# stm32h750ibk6-pwr.net
KiCad netlist of a schematic drawn in Altium Designer
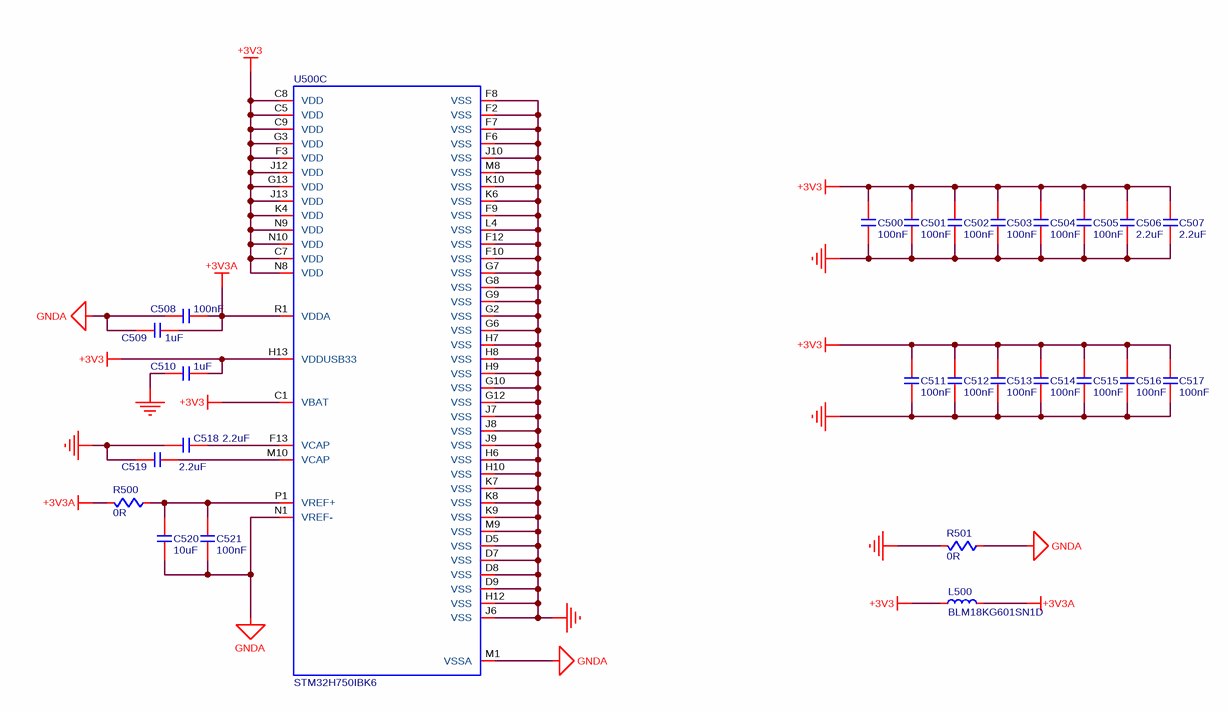
[diagram p0: stm32h750ibk6-pwr.SchDoc]

(export (version "E")
  (design (tool "Eeschema 10.0.6"))
  (components
    (comp (ref "C500")
      (value "100nF")
      (footprint "mw:C0402")
      (fields (field (name "VOLTAGE") "25V") (field (name "Comment") "C-NOMO"))
      (libsource (lib "mw") (part "C-NOMO"))
    )
    (comp (ref "C501")
      (value "100nF")
      (footprint "mw:C0402")
      (fields (field (name "VOLTAGE") "25V") (field (name "Comment") "C-NOMO"))
      (libsource (lib "mw") (part "C-NOMO"))
    )
    (comp (ref "C502")
      (value "100nF")
      (footprint "mw:C0402")
      (fields (field (name "VOLTAGE") "25V") (field (name "Comment") "C-NOMO"))
      (libsource (lib "mw") (part "C-NOMO"))
    )
    (comp (ref "C503")
      (value "100nF")
      (footprint "mw:C0402")
      (fields (field (name "VOLTAGE") "25V") (field (name "Comment") "C-NOMO"))
      (libsource (lib "mw") (part "C-NOMO"))
    )
    (comp (ref "C504")
      (value "100nF")
      (footprint "mw:C0402")
      (fields (field (name "VOLTAGE") "25V") (field (name "Comment") "C-NOMO"))
      (libsource (lib "mw") (part "C-NOMO"))
    )
    (comp (ref "C505")
      (value "100nF")
      (footprint "mw:C0402")
      (fields (field (name "VOLTAGE") "25V") (field (name "Comment") "C-NOMO"))
      (libsource (lib "mw") (part "C-NOMO"))
    )
    (comp (ref "C506")
      (value "2.2uF")
      (footprint "mw:C0603")
      (fields (field (name "VOLTAGE") "25V") (field (name "Comment") "C-NOMO"))
      (libsource (lib "mw") (part "C-NOMO"))
    )
    (comp (ref "C507")
      (value "2.2uF")
      (footprint "mw:C0603")
      (fields (field (name "VOLTAGE") "25V") (field (name "Comment") "C-NOMO"))
      (libsource (lib "mw") (part "C-NOMO"))
    )
    (comp (ref "C508")
      (value "1uF")
      (footprint "mw:C0603")
      (fields (field (name "VOLTAGE") "25V") (field (name "Comment") "C-NOMO"))
      (libsource (lib "mw") (part "C-NOMO"))
    )
    (comp (ref "C509")
      (value "100nF")
      (footprint "mw:C0402")
      (fields (field (name "VOLTAGE") "25V") (field (name "Comment") "C-NOMO"))
      (libsource (lib "mw") (part "C-NOMO"))
    )
    (comp (ref "C510")
      (value "1uF")
      (footprint "mw:C0603")
      (fields (field (name "VOLTAGE") "25V") (field (name "Comment") "C-NOMO"))
      (libsource (lib "mw") (part "C-NOMO"))
    )
    (comp (ref "C511")
      (value "100nF")
      (footprint "mw:C0402")
      (fields (field (name "VOLTAGE") "25V") (field (name "Comment") "C-NOMO"))
      (libsource (lib "mw") (part "C-NOMO"))
    )
    (comp (ref "C512")
      (value "100nF")
      (footprint "mw:C0402")
      (fields (field (name "VOLTAGE") "25V") (field (name "Comment") "C-NOMO"))
      (libsource (lib "mw") (part "C-NOMO"))
    )
    (comp (ref "C513")
      (value "100nF")
      (footprint "mw:C0402")
      (fields (field (name "VOLTAGE") "25V") (field (name "Comment") "C-NOMO"))
      (libsource (lib "mw") (part "C-NOMO"))
    )
    (comp (ref "C514")
      (value "100nF")
      (footprint "mw:C0402")
      (fields (field (name "VOLTAGE") "25V") (field (name "Comment") "C-NOMO"))
      (libsource (lib "mw") (part "C-NOMO"))
    )
    (comp (ref "C515")
      (value "100nF")
      (footprint "mw:C0402")
      (fields (field (name "VOLTAGE") "25V") (field (name "Comment") "C-NOMO"))
      (libsource (lib "mw") (part "C-NOMO"))
    )
    (comp (ref "C516")
      (value "100nF")
      (footprint "mw:C0402")
      (fields (field (name "VOLTAGE") "25V") (field (name "Comment") "C-NOMO"))
      (libsource (lib "mw") (part "C-NOMO"))
    )
    (comp (ref "C517")
      (value "100nF")
      (footprint "mw:C0402")
      (fields (field (name "VOLTAGE") "25V") (field (name "Comment") "C-NOMO"))
      (libsource (lib "mw") (part "C-NOMO"))
    )
    (comp (ref "C518")
      (value "2.2uF")
      (footprint "mw:C0603")
      (fields (field (name "VOLTAGE") "25V") (field (name "Comment") "C-NOMO"))
      (libsource (lib "mw") (part "C-NOMO"))
    )
    (comp (ref "C519")
      (value "2.2uF")
      (footprint "mw:C0603")
      (fields (field (name "VOLTAGE") "25V") (field (name "Comment") "C-NOMO"))
      (libsource (lib "mw") (part "C-NOMO"))
    )
    (comp (ref "C520")
      (value "10uF")
      (footprint "mw:C0603")
      (fields (field (name "VOLTAGE") "25V") (field (name "Comment") "C-NOMO"))
      (libsource (lib "mw") (part "C-NOMO"))
    )
    (comp (ref "C521")
      (value "100nF")
      (footprint "mw:C0402")
      (fields (field (name "VOLTAGE") "25V") (field (name "Comment") "C-NOMO"))
      (libsource (lib "mw") (part "C-NOMO"))
    )
    (comp (ref "L500")
      (value "BLM18KG601SN1D")
      (footprint "mw:L0603")
      (fields (field (name "PUBLISHER") "Altium Limited"))
      (libsource (lib "mw") (part "L"))
    )
    (comp (ref "R500")
      (value "0R")
      (footprint "mw:R0603")
      (fields (field (name "Comment") "R"))
      (libsource (lib "mw") (part "R"))
    )
    (comp (ref "R501")
      (value "0R")
      (footprint "mw:R0603")
      (fields (field (name "Comment") "R"))
      (libsource (lib "mw") (part "R"))
    )
    (comp (ref "U500")
      (value "STM32H750IBK6")
      (footprint "mw:STM32H750IBK6")
      (libsource (lib "mw") (part "STM32H750IBK6"))
    )
  )
  (nets
    (net (code "1") (name "+3V3") (class "Default")
      (node (ref "C500") (pin "2") (pinfunction "2_2") (pintype "passive"))
      (node (ref "C501") (pin "2") (pinfunction "2_2") (pintype "passive"))
      (node (ref "C502") (pin "2") (pinfunction "2_2") (pintype "passive"))
      (node (ref "C503") (pin "2") (pinfunction "2_2") (pintype "passive"))
      (node (ref "C504") (pin "2") (pinfunction "2_2") (pintype "passive"))
      (node (ref "C505") (pin "2") (pinfunction "2_2") (pintype "passive"))
      (node (ref "C506") (pin "2") (pinfunction "2_2") (pintype "passive"))
      (node (ref "C507") (pin "2") (pinfunction "2_2") (pintype "passive"))
      (node (ref "C510") (pin "1") (pinfunction "1_1") (pintype "passive"))
      (node (ref "C511") (pin "2") (pinfunction "2_2") (pintype "passive"))
      (node (ref "C512") (pin "2") (pinfunction "2_2") (pintype "passive"))
      (node (ref "C513") (pin "2") (pinfunction "2_2") (pintype "passive"))
      (node (ref "C514") (pin "2") (pinfunction "2_2") (pintype "passive"))
      (node (ref "C515") (pin "2") (pinfunction "2_2") (pintype "passive"))
      (node (ref "C516") (pin "2") (pinfunction "2_2") (pintype "passive"))
      (node (ref "C517") (pin "2") (pinfunction "2_2") (pintype "passive"))
      (node (ref "L500") (pin "1") (pinfunction "1_1") (pintype "passive"))
      (node (ref "U500") (pin "C1") (pinfunction "VBAT_C1") (pintype "passive"))
      (node (ref "U500") (pin "C5") (pinfunction "VDD_C5") (pintype "passive"))
      (node (ref "U500") (pin "C7") (pinfunction "VDD_C7") (pintype "passive"))
      (node (ref "U500") (pin "C8") (pinfunction "VDD_C8") (pintype "passive"))
      (node (ref "U500") (pin "C9") (pinfunction "VDD_C9") (pintype "passive"))
      (node (ref "U500") (pin "F3") (pinfunction "VDD_F3") (pintype "passive"))
      (node (ref "U500") (pin "G13") (pinfunction "VDD_G13") (pintype "passive"))
      (node (ref "U500") (pin "G3") (pinfunction "VDD_G3") (pintype "passive"))
      (node (ref "U500") (pin "H13") (pinfunction "VDDUSB33_H13") (pintype "passive"))
      (node (ref "U500") (pin "J12") (pinfunction "VDD_J12") (pintype "passive"))
      (node (ref "U500") (pin "J13") (pinfunction "VDD_J13") (pintype "passive"))
      (node (ref "U500") (pin "K4") (pinfunction "VDD_K4") (pintype "passive"))
      (node (ref "U500") (pin "N10") (pinfunction "VDD_N10") (pintype "passive"))
      (node (ref "U500") (pin "N8") (pinfunction "VDD_N8") (pintype "passive"))
      (node (ref "U500") (pin "N9") (pinfunction "VDD_N9") (pintype "passive"))
    )
    (net (code "2") (name "+3V3A") (class "Default")
      (node (ref "C508") (pin "1") (pinfunction "1_1") (pintype "passive"))
      (node (ref "C509") (pin "1") (pinfunction "1_1") (pintype "passive"))
      (node (ref "L500") (pin "2") (pinfunction "2_2") (pintype "passive"))
      (node (ref "R500") (pin "1") (pinfunction "1_1") (pintype "passive"))
      (node (ref "U500") (pin "R1") (pinfunction "VDDA_R1") (pintype "passive"))
    )
    (net (code "3") (name "GND") (class "Default")
      (node (ref "C500") (pin "1") (pinfunction "1_1") (pintype "passive"))
      (node (ref "C501") (pin "1") (pinfunction "1_1") (pintype "passive"))
      (node (ref "C502") (pin "1") (pinfunction "1_1") (pintype "passive"))
      (node (ref "C503") (pin "1") (pinfunction "1_1") (pintype "passive"))
      (node (ref "C504") (pin "1") (pinfunction "1_1") (pintype "passive"))
      (node (ref "C505") (pin "1") (pinfunction "1_1") (pintype "passive"))
      (node (ref "C506") (pin "1") (pinfunction "1_1") (pintype "passive"))
      (node (ref "C507") (pin "1") (pinfunction "1_1") (pintype "passive"))
      (node (ref "C510") (pin "2") (pinfunction "2_2") (pintype "passive"))
      (node (ref "C511") (pin "1") (pinfunction "1_1") (pintype "passive"))
      (node (ref "C512") (pin "1") (pinfunction "1_1") (pintype "passive"))
      (node (ref "C513") (pin "1") (pinfunction "1_1") (pintype "passive"))
      (node (ref "C514") (pin "1") (pinfunction "1_1") (pintype "passive"))
      (node (ref "C515") (pin "1") (pinfunction "1_1") (pintype "passive"))
      (node (ref "C516") (pin "1") (pinfunction "1_1") (pintype "passive"))
      (node (ref "C517") (pin "1") (pinfunction "1_1") (pintype "passive"))
      (node (ref "C518") (pin "1") (pinfunction "1_1") (pintype "passive"))
      (node (ref "C519") (pin "1") (pinfunction "1_1") (pintype "passive"))
      (node (ref "R501") (pin "1") (pinfunction "1_1") (pintype "passive"))
      (node (ref "U500") (pin "D5") (pinfunction "VSS_D5") (pintype "passive"))
      (node (ref "U500") (pin "D7") (pinfunction "VSS_D7") (pintype "passive"))
      (node (ref "U500") (pin "D8") (pinfunction "VSS_D8") (pintype "passive"))
      (node (ref "U500") (pin "D9") (pinfunction "VSS_D9") (pintype "passive"))
      (node (ref "U500") (pin "F10") (pinfunction "VSS_F10") (pintype "passive"))
      (node (ref "U500") (pin "F12") (pinfunction "VSS_F12") (pintype "passive"))
      (node (ref "U500") (pin "F2") (pinfunction "VSS_F2") (pintype "passive"))
      (node (ref "U500") (pin "F6") (pinfunction "VSS_F6") (pintype "passive"))
      (node (ref "U500") (pin "F7") (pinfunction "VSS_F7") (pintype "passive"))
      (node (ref "U500") (pin "F8") (pinfunction "VSS_F8") (pintype "passive"))
      (node (ref "U500") (pin "F9") (pinfunction "VSS_F9") (pintype "passive"))
      (node (ref "U500") (pin "G10") (pinfunction "VSS_G10") (pintype "passive"))
      (node (ref "U500") (pin "G12") (pinfunction "VSS_G12") (pintype "passive"))
      (node (ref "U500") (pin "G2") (pinfunction "VSS_G2") (pintype "passive"))
      (node (ref "U500") (pin "G6") (pinfunction "VSS_G6") (pintype "passive"))
      (node (ref "U500") (pin "G7") (pinfunction "VSS_G7") (pintype "passive"))
      (node (ref "U500") (pin "G8") (pinfunction "VSS_G8") (pintype "passive"))
      (node (ref "U500") (pin "G9") (pinfunction "VSS_G9") (pintype "passive"))
      (node (ref "U500") (pin "H10") (pinfunction "VSS_H10") (pintype "passive"))
      (node (ref "U500") (pin "H12") (pinfunction "VSS_H12") (pintype "passive"))
      (node (ref "U500") (pin "H6") (pinfunction "VSS_H6") (pintype "passive"))
      (node (ref "U500") (pin "H7") (pinfunction "VSS_H7") (pintype "passive"))
      (node (ref "U500") (pin "H8") (pinfunction "VSS_H8") (pintype "passive"))
      (node (ref "U500") (pin "H9") (pinfunction "VSS_H9") (pintype "passive"))
      (node (ref "U500") (pin "J10") (pinfunction "VSS_J10") (pintype "passive"))
      (node (ref "U500") (pin "J6") (pinfunction "VSS_J6") (pintype "passive"))
      (node (ref "U500") (pin "J7") (pinfunction "VSS_J7") (pintype "passive"))
      (node (ref "U500") (pin "J8") (pinfunction "VSS_J8") (pintype "passive"))
      (node (ref "U500") (pin "J9") (pinfunction "VSS_J9") (pintype "passive"))
      (node (ref "U500") (pin "K10") (pinfunction "VSS_K10") (pintype "passive"))
      (node (ref "U500") (pin "K6") (pinfunction "VSS_K6") (pintype "passive"))
      (node (ref "U500") (pin "K7") (pinfunction "VSS_K7") (pintype "passive"))
      (node (ref "U500") (pin "K8") (pinfunction "VSS_K8") (pintype "passive"))
      (node (ref "U500") (pin "K9") (pinfunction "VSS_K9") (pintype "passive"))
      (node (ref "U500") (pin "L4") (pinfunction "VSS_L4") (pintype "passive"))
      (node (ref "U500") (pin "M8") (pinfunction "VSS_M8") (pintype "passive"))
      (node (ref "U500") (pin "M9") (pinfunction "VSS_M9") (pintype "passive"))
    )
    (net (code "4") (name "GNDA") (class "Default")
      (node (ref "C508") (pin "2") (pinfunction "2_2") (pintype "passive"))
      (node (ref "C509") (pin "2") (pinfunction "2_2") (pintype "passive"))
      (node (ref "C520") (pin "1") (pinfunction "1_1") (pintype "passive"))
      (node (ref "C521") (pin "1") (pinfunction "1_1") (pintype "passive"))
      (node (ref "R501") (pin "2") (pinfunction "2_2") (pintype "passive"))
      (node (ref "U500") (pin "M1") (pinfunction "VSSA_M1") (pintype "passive"))
      (node (ref "U500") (pin "N1") (pinfunction "VREF-_N1") (pintype "passive"))
    )
    (net (code "5") (name "Net-(C518-Pad2)") (class "Default")
      (node (ref "C518") (pin "2") (pinfunction "2_2") (pintype "passive"))
      (node (ref "U500") (pin "F13") (pinfunction "VCAP_F13") (pintype "passive"))
    )
    (net (code "6") (name "Net-(C519-Pad2)") (class "Default")
      (node (ref "C519") (pin "2") (pinfunction "2_2") (pintype "passive"))
      (node (ref "U500") (pin "M10") (pinfunction "VCAP_M10") (pintype "passive"))
    )
    (net (code "7") (name "Net-(U500C-VREF+)") (class "Default")
      (node (ref "C520") (pin "2") (pinfunction "2_2") (pintype "passive"))
      (node (ref "C521") (pin "2") (pinfunction "2_2") (pintype "passive"))
      (node (ref "R500") (pin "2") (pinfunction "2_2") (pintype "passive"))
      (node (ref "U500") (pin "P1") (pinfunction "VREF+_P1") (pintype "passive"))
    )
  )
)
